# MainBoard.net
KiCad netlist of a schematic drawn in EAGLE
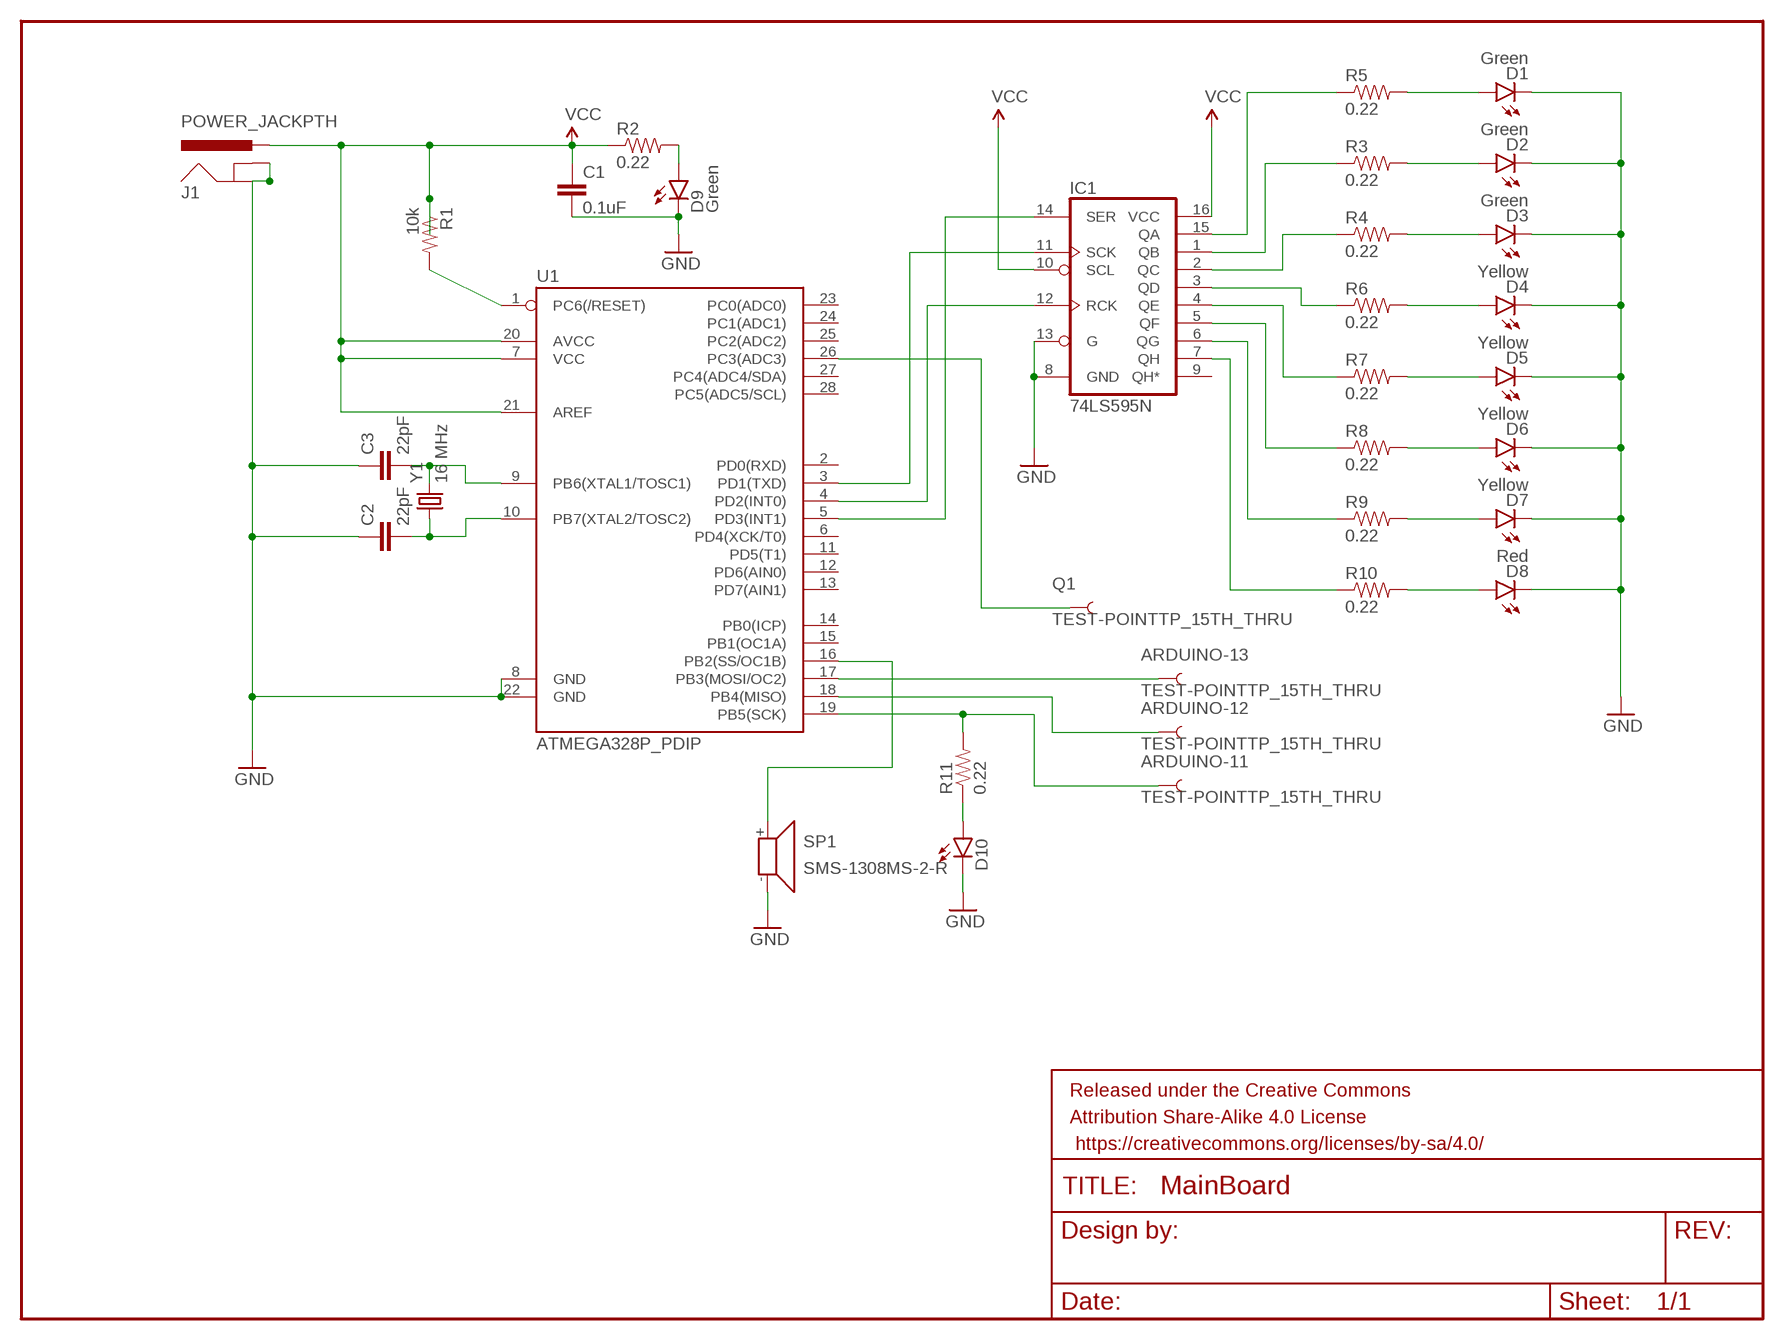
[diagram p0: schematic, sheet 1]

(export (version "E")
  (design (tool "Eeschema 10.0.6"))
  (components
    (comp (ref "ARDUINO-11")
      (value "TEST-POINTTP_15TH_THRU")
      (footprint "eagle-import:TP_15TH")
      (libsource (lib "eagle-import") (part "TEST-POINTTP_15TH_THRU"))
    )
    (comp (ref "ARDUINO-12")
      (value "TEST-POINTTP_15TH_THRU")
      (footprint "eagle-import:TP_15TH")
      (libsource (lib "eagle-import") (part "TEST-POINTTP_15TH_THRU"))
    )
    (comp (ref "ARDUINO-13")
      (value "TEST-POINTTP_15TH_THRU")
      (footprint "eagle-import:TP_15TH")
      (libsource (lib "eagle-import") (part "TEST-POINTTP_15TH_THRU"))
    )
    (comp (ref "C1")
      (value "0.1uF")
      (footprint "eagle-import:0402-CAP")
      (libsource (lib "eagle-import") (part "0.1UF-16V(+-10%)(0402)"))
    )
    (comp (ref "C2")
      (value "22pF")
      (footprint "eagle-import:0603-CAP")
      (libsource (lib "eagle-import") (part "22PF-50V-5%(0603)"))
    )
    (comp (ref "C3")
      (value "22pF")
      (footprint "eagle-import:0603-CAP")
      (libsource (lib "eagle-import") (part "22PF-50V-5%(0603)"))
    )
    (comp (ref "D1")
      (value "Green")
      (footprint "eagle-import:LED5MM")
      (libsource (lib "eagle-import") (part "LED5MM"))
    )
    (comp (ref "D2")
      (value "Green")
      (footprint "eagle-import:LED5MM")
      (libsource (lib "eagle-import") (part "LED5MM"))
    )
    (comp (ref "D3")
      (value "Green")
      (footprint "eagle-import:LED5MM")
      (libsource (lib "eagle-import") (part "LED5MM"))
    )
    (comp (ref "D4")
      (value "Yellow")
      (footprint "eagle-import:LED5MM")
      (libsource (lib "eagle-import") (part "LED5MM"))
    )
    (comp (ref "D5")
      (value "Yellow")
      (footprint "eagle-import:LED5MM")
      (libsource (lib "eagle-import") (part "LED5MM"))
    )
    (comp (ref "D6")
      (value "Yellow")
      (footprint "eagle-import:LED5MM")
      (libsource (lib "eagle-import") (part "LED5MM"))
    )
    (comp (ref "D7")
      (value "Yellow")
      (footprint "eagle-import:LED5MM")
      (libsource (lib "eagle-import") (part "LED5MM"))
    )
    (comp (ref "D8")
      (value "Red")
      (footprint "eagle-import:LED5MM")
      (libsource (lib "eagle-import") (part "LED5MM"))
    )
    (comp (ref "D9")
      (value "Green")
      (footprint "eagle-import:LED3MM")
      (libsource (lib "eagle-import") (part "LED3MM"))
    )
    (comp (ref "D10")
      (value "LED5MM")
      (footprint "eagle-import:LED5MM")
      (libsource (lib "eagle-import") (part "LED5MM"))
    )
    (comp (ref "FRAME1")
      (value "FRAME-LETTER")
      (footprint "eagle-import:CREATIVE_COMMONS")
      (libsource (lib "eagle-import") (part "FRAME-LETTER"))
    )
    (comp (ref "IC1")
      (value "74LS595N")
      (footprint "eagle-import:DIL16")
      (libsource (lib "eagle-import") (part "74595NLS"))
    )
    (comp (ref "J1")
      (value "POWER_JACKPTH")
      (footprint "eagle-import:POWER_JACK_PTH")
      (libsource (lib "eagle-import") (part "POWER_JACKPTH"))
    )
    (comp (ref "Q1")
      (value "TEST-POINTTP_15TH_THRU")
      (footprint "eagle-import:TP_15TH")
      (libsource (lib "eagle-import") (part "TEST-POINTTP_15TH_THRU"))
    )
    (comp (ref "R1")
      (value "10k")
      (footprint "eagle-import:AXIAL-0.3")
      (libsource (lib "eagle-import") (part "10KOHM-1/4W5%(PTH)"))
    )
    (comp (ref "R2")
      (value "0.22")
      (footprint "eagle-import:0805")
      (libsource (lib "eagle-import") (part "0.22OHM-1/4W-1%(0805)"))
    )
    (comp (ref "R3")
      (value "0.22")
      (footprint "eagle-import:0805")
      (libsource (lib "eagle-import") (part "0.22OHM-1/4W-1%(0805)"))
    )
    (comp (ref "R4")
      (value "0.22")
      (footprint "eagle-import:0805")
      (libsource (lib "eagle-import") (part "0.22OHM-1/4W-1%(0805)"))
    )
    (comp (ref "R5")
      (value "0.22")
      (footprint "eagle-import:0805")
      (libsource (lib "eagle-import") (part "0.22OHM-1/4W-1%(0805)"))
    )
    (comp (ref "R6")
      (value "0.22")
      (footprint "eagle-import:0805")
      (libsource (lib "eagle-import") (part "0.22OHM-1/4W-1%(0805)"))
    )
    (comp (ref "R7")
      (value "0.22")
      (footprint "eagle-import:0805")
      (libsource (lib "eagle-import") (part "0.22OHM-1/4W-1%(0805)"))
    )
    (comp (ref "R8")
      (value "0.22")
      (footprint "eagle-import:0805")
      (libsource (lib "eagle-import") (part "0.22OHM-1/4W-1%(0805)"))
    )
    (comp (ref "R9")
      (value "0.22")
      (footprint "eagle-import:0805")
      (libsource (lib "eagle-import") (part "0.22OHM-1/4W-1%(0805)"))
    )
    (comp (ref "R10")
      (value "0.22")
      (footprint "eagle-import:0805")
      (libsource (lib "eagle-import") (part "0.22OHM-1/4W-1%(0805)"))
    )
    (comp (ref "R11")
      (value "0.22")
      (footprint "eagle-import:0805")
      (libsource (lib "eagle-import") (part "0.22OHM-1/4W-1%(0805)"))
    )
    (comp (ref "SP1")
      (value "SMS-1308MS-2-R")
      (footprint "eagle-import:SMS-1308MS-2-R")
      (libsource (lib "eagle-import") (part "SMS-1308MS-2-R"))
    )
    (comp (ref "U1")
      (value "ATMEGA328P_PDIP")
      (footprint "eagle-import:DIL28-3")
      (libsource (lib "eagle-import") (part "ATMEGA328P_PDIP"))
    )
    (comp (ref "Y1")
      (value "16 MHz")
      (footprint "eagle-import:HC49US")
      (libsource (lib "eagle-import") (part "CRYSTALHC49US"))
    )
  )
  (nets
    (net (code "1") (name "GND") (class "Default")
      (node (ref "C1") (pin "2") (pinfunction "2_2") (pintype "passive"))
      (node (ref "C2") (pin "1") (pinfunction "1_1") (pintype "passive"))
      (node (ref "C3") (pin "1") (pinfunction "1_1") (pintype "passive"))
      (node (ref "D1") (pin "K") (pinfunction "C_K") (pintype "passive"))
      (node (ref "D10") (pin "K") (pinfunction "C_K") (pintype "passive"))
      (node (ref "D2") (pin "K") (pinfunction "C_K") (pintype "passive"))
      (node (ref "D3") (pin "K") (pinfunction "C_K") (pintype "passive"))
      (node (ref "D4") (pin "K") (pinfunction "C_K") (pintype "passive"))
      (node (ref "D5") (pin "K") (pinfunction "C_K") (pintype "passive"))
      (node (ref "D6") (pin "K") (pinfunction "C_K") (pintype "passive"))
      (node (ref "D7") (pin "K") (pinfunction "C_K") (pintype "passive"))
      (node (ref "D8") (pin "K") (pinfunction "C_K") (pintype "passive"))
      (node (ref "D9") (pin "K") (pinfunction "C_K") (pintype "passive"))
      (node (ref "IC1") (pin "13") (pinfunction "G_13") (pintype "input"))
      (node (ref "IC1") (pin "8") (pinfunction "GND_8") (pintype "power_in"))
      (node (ref "J1") (pin "GND") (pinfunction "GND_GND") (pintype "bidirectional"))
      (node (ref "J1") (pin "GNDBREAK") (pinfunction "GNDBREAK_GNDBREAK") (pintype "bidirectional"))
      (node (ref "SP1") (pin "-") (pinfunction "2_-") (pintype "passive"))
      (node (ref "U1") (pin "22") (pinfunction "GND_22") (pintype "bidirectional"))
      (node (ref "U1") (pin "8") (pinfunction "GND_8") (pintype "bidirectional"))
    )
    (net (code "2") (name "Net-(ARDUINO-11-1)") (class "Default")
      (node (ref "ARDUINO-11") (pin "P$1") (pinfunction "1_P$1") (pintype "bidirectional"))
      (node (ref "R11") (pin "2") (pinfunction "2_2") (pintype "passive"))
      (node (ref "U1") (pin "19") (pinfunction "PB5(SCK)_19") (pintype "bidirectional"))
    )
    (net (code "3") (name "Net-(ARDUINO-12-1)") (class "Default")
      (node (ref "ARDUINO-12") (pin "P$1") (pinfunction "1_P$1") (pintype "bidirectional"))
      (node (ref "U1") (pin "18") (pinfunction "PB4(MISO)_18") (pintype "bidirectional"))
    )
    (net (code "4") (name "Net-(ARDUINO-13-1)") (class "Default")
      (node (ref "ARDUINO-13") (pin "P$1") (pinfunction "1_P$1") (pintype "bidirectional"))
      (node (ref "U1") (pin "17") (pinfunction "PB3(MOSI/OC2)_17") (pintype "bidirectional"))
    )
    (net (code "5") (name "Net-(D1-PadA)") (class "Default")
      (node (ref "D1") (pin "A") (pinfunction "A_A") (pintype "passive"))
      (node (ref "R5") (pin "2") (pinfunction "2_2") (pintype "passive"))
    )
    (net (code "6") (name "Net-(D2-PadA)") (class "Default")
      (node (ref "D2") (pin "A") (pinfunction "A_A") (pintype "passive"))
      (node (ref "R3") (pin "2") (pinfunction "2_2") (pintype "passive"))
    )
    (net (code "7") (name "Net-(D3-PadA)") (class "Default")
      (node (ref "D3") (pin "A") (pinfunction "A_A") (pintype "passive"))
      (node (ref "R4") (pin "2") (pinfunction "2_2") (pintype "passive"))
    )
    (net (code "8") (name "Net-(D4-PadA)") (class "Default")
      (node (ref "D4") (pin "A") (pinfunction "A_A") (pintype "passive"))
      (node (ref "R6") (pin "2") (pinfunction "2_2") (pintype "passive"))
    )
    (net (code "9") (name "Net-(D5-PadA)") (class "Default")
      (node (ref "D5") (pin "A") (pinfunction "A_A") (pintype "passive"))
      (node (ref "R7") (pin "2") (pinfunction "2_2") (pintype "passive"))
    )
    (net (code "10") (name "Net-(D6-PadA)") (class "Default")
      (node (ref "D6") (pin "A") (pinfunction "A_A") (pintype "passive"))
      (node (ref "R8") (pin "2") (pinfunction "2_2") (pintype "passive"))
    )
    (net (code "11") (name "Net-(D7-PadA)") (class "Default")
      (node (ref "D7") (pin "A") (pinfunction "A_A") (pintype "passive"))
      (node (ref "R9") (pin "2") (pinfunction "2_2") (pintype "passive"))
    )
    (net (code "12") (name "Net-(D8-PadA)") (class "Default")
      (node (ref "D8") (pin "A") (pinfunction "A_A") (pintype "passive"))
      (node (ref "R10") (pin "2") (pinfunction "2_2") (pintype "passive"))
    )
    (net (code "13") (name "Net-(D9-PadA)") (class "Default")
      (node (ref "D9") (pin "A") (pinfunction "A_A") (pintype "passive"))
      (node (ref "R2") (pin "2") (pinfunction "2_2") (pintype "passive"))
    )
    (net (code "14") (name "Net-(D10-PadA)") (class "Default")
      (node (ref "D10") (pin "A") (pinfunction "A_A") (pintype "passive"))
      (node (ref "R11") (pin "1") (pinfunction "1_1") (pintype "passive"))
    )
    (net (code "15") (name "Net-(IC1-QA)") (class "Default")
      (node (ref "IC1") (pin "15") (pinfunction "QA_15") (pintype "tri_state"))
      (node (ref "R5") (pin "1") (pinfunction "1_1") (pintype "passive"))
    )
    (net (code "16") (name "Net-(IC1-QB)") (class "Default")
      (node (ref "IC1") (pin "1") (pinfunction "QB_1") (pintype "tri_state"))
      (node (ref "R3") (pin "1") (pinfunction "1_1") (pintype "passive"))
    )
    (net (code "17") (name "Net-(IC1-QC)") (class "Default")
      (node (ref "IC1") (pin "2") (pinfunction "QC_2") (pintype "tri_state"))
      (node (ref "R4") (pin "1") (pinfunction "1_1") (pintype "passive"))
    )
    (net (code "18") (name "Net-(IC1-QD)") (class "Default")
      (node (ref "IC1") (pin "3") (pinfunction "QD_3") (pintype "tri_state"))
      (node (ref "R6") (pin "1") (pinfunction "1_1") (pintype "passive"))
    )
    (net (code "19") (name "Net-(IC1-QE)") (class "Default")
      (node (ref "IC1") (pin "4") (pinfunction "QE_4") (pintype "tri_state"))
      (node (ref "R7") (pin "1") (pinfunction "1_1") (pintype "passive"))
    )
    (net (code "20") (name "Net-(IC1-QF)") (class "Default")
      (node (ref "IC1") (pin "5") (pinfunction "QF_5") (pintype "tri_state"))
      (node (ref "R8") (pin "1") (pinfunction "1_1") (pintype "passive"))
    )
    (net (code "21") (name "Net-(IC1-QG)") (class "Default")
      (node (ref "IC1") (pin "6") (pinfunction "QG_6") (pintype "tri_state"))
      (node (ref "R9") (pin "1") (pinfunction "1_1") (pintype "passive"))
    )
    (net (code "22") (name "Net-(IC1-QH)") (class "Default")
      (node (ref "IC1") (pin "7") (pinfunction "QH_7") (pintype "tri_state"))
      (node (ref "R10") (pin "1") (pinfunction "1_1") (pintype "passive"))
    )
    (net (code "23") (name "Net-(IC1-RCK)") (class "Default")
      (node (ref "IC1") (pin "12") (pinfunction "RCK_12") (pintype "input"))
      (node (ref "U1") (pin "4") (pinfunction "PD2(INT0)_4") (pintype "bidirectional"))
    )
    (net (code "24") (name "Net-(IC1-SCK)") (class "Default")
      (node (ref "IC1") (pin "11") (pinfunction "SCK_11") (pintype "input"))
      (node (ref "U1") (pin "3") (pinfunction "PD1(TXD)_3") (pintype "bidirectional"))
    )
    (net (code "25") (name "Net-(IC1-SER)") (class "Default")
      (node (ref "IC1") (pin "14") (pinfunction "SER_14") (pintype "input"))
      (node (ref "U1") (pin "5") (pinfunction "PD3(INT1)_5") (pintype "bidirectional"))
    )
    (net (code "26") (name "Net-(Q1-1)") (class "Default")
      (node (ref "Q1") (pin "P$1") (pinfunction "1_P$1") (pintype "bidirectional"))
      (node (ref "U1") (pin "26") (pinfunction "PC3(ADC3)_26") (pintype "bidirectional"))
    )
    (net (code "27") (name "Net-(R1-2)") (class "Default")
      (node (ref "R1") (pin "P$2") (pinfunction "2_P$2") (pintype "passive"))
      (node (ref "U1") (pin "1") (pinfunction "PC6(/RESET)_1") (pintype "bidirectional"))
    )
    (net (code "28") (name "Net-(SP1-1)") (class "Default")
      (node (ref "SP1") (pin "+") (pinfunction "1_+") (pintype "passive"))
      (node (ref "U1") (pin "16") (pinfunction "PB2(SS/OC1B)_16") (pintype "bidirectional"))
    )
    (net (code "29") (name "Net-(U1-PB6(XTAL1{slash}TOSC1))") (class "Default")
      (node (ref "C3") (pin "2") (pinfunction "2_2") (pintype "passive"))
      (node (ref "U1") (pin "9") (pinfunction "PB6(XTAL1/TOSC1)_9") (pintype "bidirectional"))
      (node (ref "Y1") (pin "2") (pinfunction "2_2") (pintype "passive"))
    )
    (net (code "30") (name "Net-(U1-PB7(XTAL2{slash}TOSC2))") (class "Default")
      (node (ref "C2") (pin "2") (pinfunction "2_2") (pintype "passive"))
      (node (ref "U1") (pin "10") (pinfunction "PB7(XTAL2/TOSC2)_10") (pintype "bidirectional"))
      (node (ref "Y1") (pin "1") (pinfunction "1_1") (pintype "passive"))
    )
    (net (code "31") (name "VCC") (class "Default")
      (node (ref "C1") (pin "1") (pinfunction "1_1") (pintype "passive"))
      (node (ref "IC1") (pin "10") (pinfunction "SCL_10") (pintype "input"))
      (node (ref "IC1") (pin "16") (pinfunction "VCC_16") (pintype "power_in"))
      (node (ref "J1") (pin "PWR") (pinfunction "PWR_PWR") (pintype "bidirectional"))
      (node (ref "R1") (pin "P$1") (pinfunction "1_P$1") (pintype "passive"))
      (node (ref "R2") (pin "1") (pinfunction "1_1") (pintype "passive"))
      (node (ref "U1") (pin "20") (pinfunction "AVCC_20") (pintype "bidirectional"))
      (node (ref "U1") (pin "21") (pinfunction "AREF_21") (pintype "bidirectional"))
      (node (ref "U1") (pin "7") (pinfunction "VCC_7") (pintype "bidirectional"))
    )
    (net (code "32") (name "unconnected-(IC1-QH*-Pad9)") (class "Default")
      (node (ref "IC1") (pin "9") (pinfunction "QH*_9") (pintype "tri_state"))
    )
    (net (code "33") (name "unconnected-(U1-PB0(ICP)-Pad14)") (class "Default")
      (node (ref "U1") (pin "14") (pinfunction "PB0(ICP)_14") (pintype "bidirectional"))
    )
    (net (code "34") (name "unconnected-(U1-PB1(OC1A)-Pad15)") (class "Default")
      (node (ref "U1") (pin "15") (pinfunction "PB1(OC1A)_15") (pintype "bidirectional"))
    )
    (net (code "35") (name "unconnected-(U1-PC0(ADC0)-Pad23)") (class "Default")
      (node (ref "U1") (pin "23") (pinfunction "PC0(ADC0)_23") (pintype "bidirectional"))
    )
    (net (code "36") (name "unconnected-(U1-PC1(ADC1)-Pad24)") (class "Default")
      (node (ref "U1") (pin "24") (pinfunction "PC1(ADC1)_24") (pintype "bidirectional"))
    )
    (net (code "37") (name "unconnected-(U1-PC2(ADC2)-Pad25)") (class "Default")
      (node (ref "U1") (pin "25") (pinfunction "PC2(ADC2)_25") (pintype "bidirectional"))
    )
    (net (code "38") (name "unconnected-(U1-PC4(ADC4{slash}SDA)-Pad27)") (class "Default")
      (node (ref "U1") (pin "27") (pinfunction "PC4(ADC4/SDA)_27") (pintype "bidirectional"))
    )
    (net (code "39") (name "unconnected-(U1-PC5(ADC5{slash}SCL)-Pad28)") (class "Default")
      (node (ref "U1") (pin "28") (pinfunction "PC5(ADC5/SCL)_28") (pintype "bidirectional"))
    )
    (net (code "40") (name "unconnected-(U1-PD0(RXD)-Pad2)") (class "Default")
      (node (ref "U1") (pin "2") (pinfunction "PD0(RXD)_2") (pintype "bidirectional"))
    )
    (net (code "41") (name "unconnected-(U1-PD4(XCK{slash}T0)-Pad6)") (class "Default")
      (node (ref "U1") (pin "6") (pinfunction "PD4(XCK/T0)_6") (pintype "bidirectional"))
    )
    (net (code "42") (name "unconnected-(U1-PD5(T1)-Pad11)") (class "Default")
      (node (ref "U1") (pin "11") (pinfunction "PD5(T1)_11") (pintype "bidirectional"))
    )
    (net (code "43") (name "unconnected-(U1-PD6(AIN0)-Pad12)") (class "Default")
      (node (ref "U1") (pin "12") (pinfunction "PD6(AIN0)_12") (pintype "bidirectional"))
    )
    (net (code "44") (name "unconnected-(U1-PD7(AIN1)-Pad13)") (class "Default")
      (node (ref "U1") (pin "13") (pinfunction "PD7(AIN1)_13") (pintype "bidirectional"))
    )
  )
)
